# USBSocket_Type1_v1_0.net
KiCad netlist of a schematic drawn in EAGLE
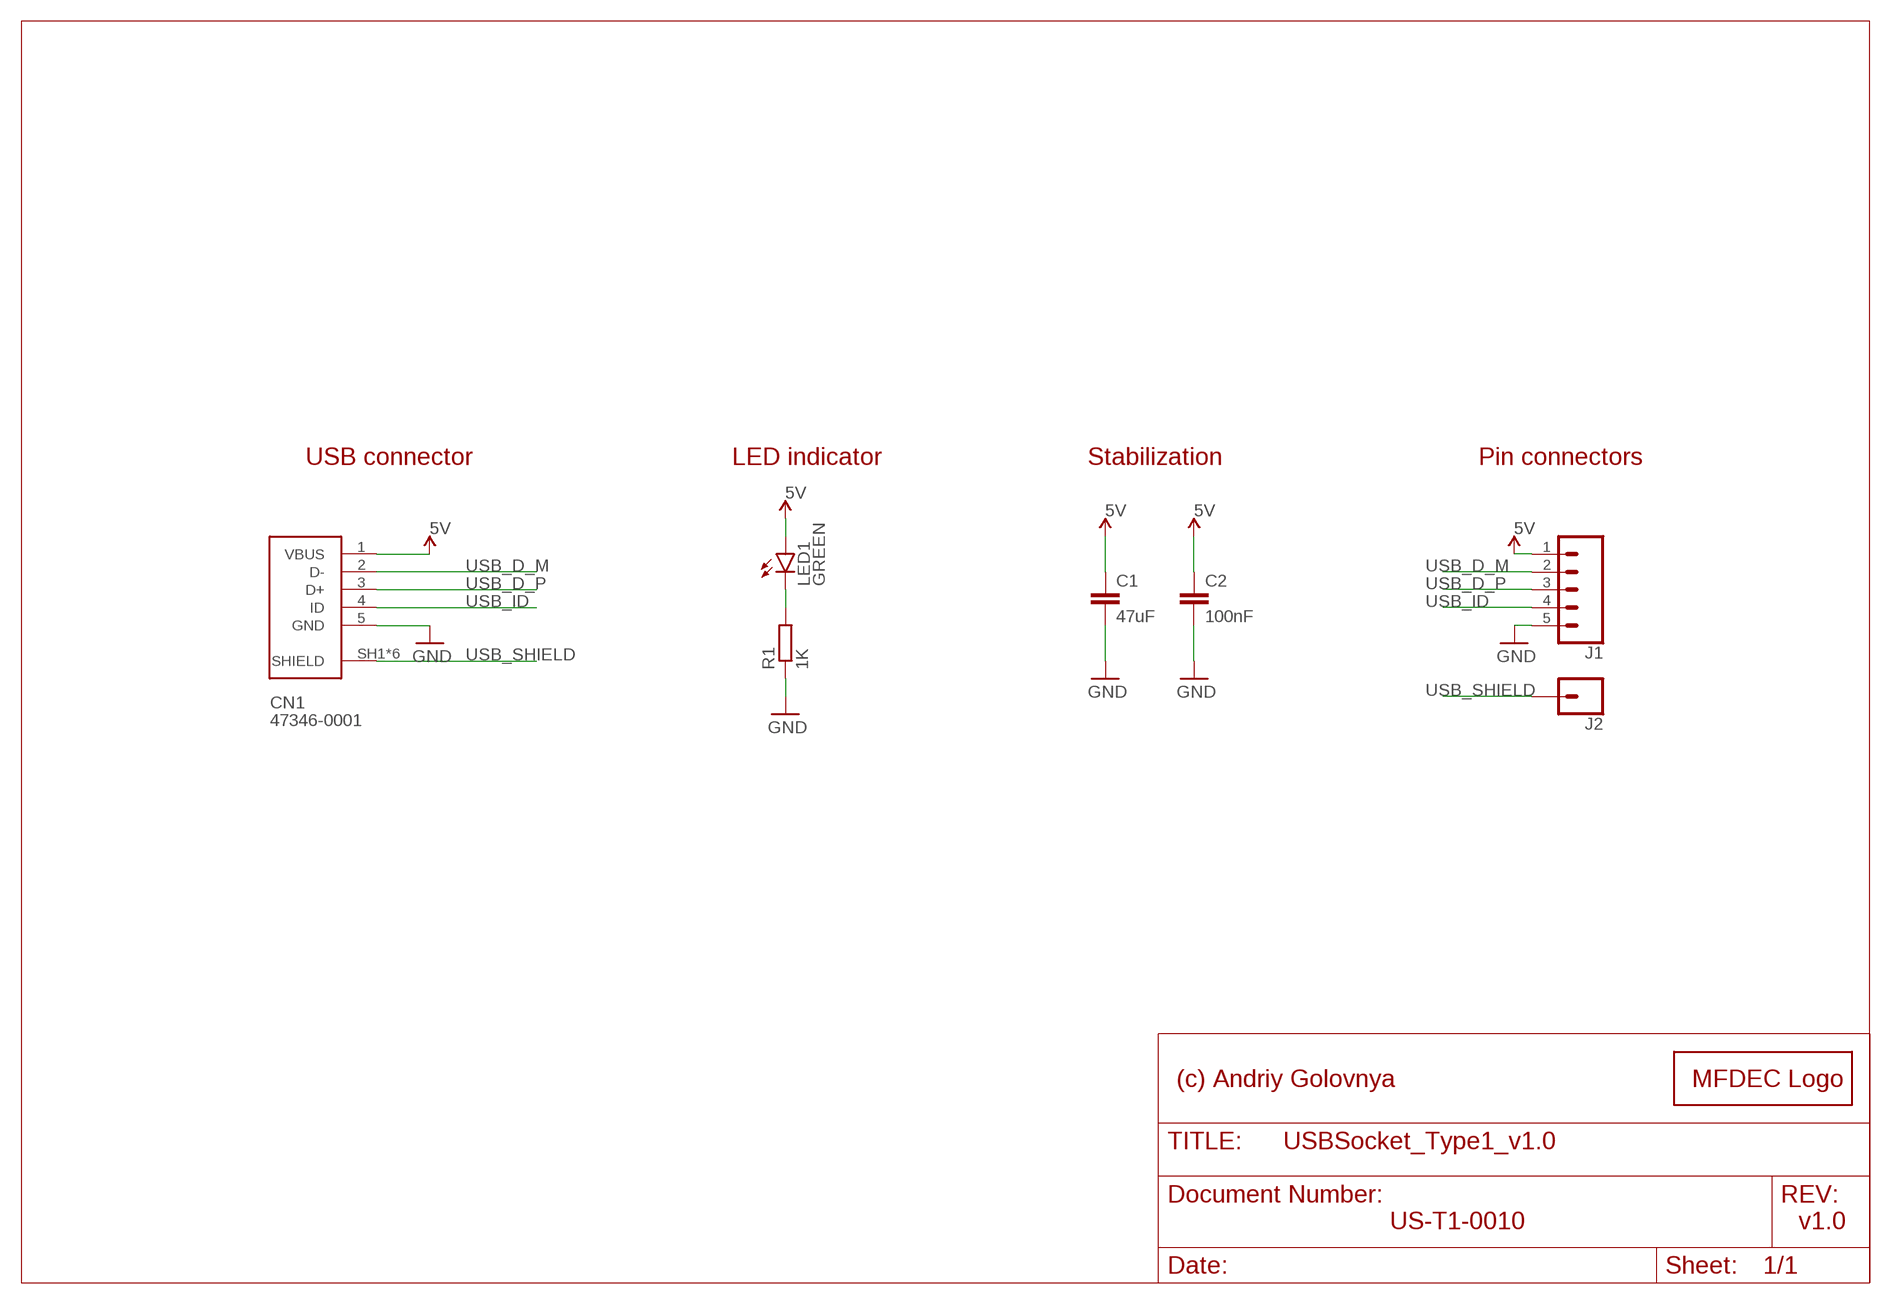
[diagram p0: schematic, sheet 1]

(export (version "E")
  (design (tool "Eeschema 10.0.6"))
  (components
    (comp (ref "C1")
      (value "47uF")
      (footprint "eagle-import:C0805")
      (libsource (lib "eagle-import") (part "C-EUC0805"))
    )
    (comp (ref "C2")
      (value "100nF")
      (footprint "eagle-import:C0402")
      (libsource (lib "eagle-import") (part "C-EUC0402"))
    )
    (comp (ref "CN1")
      (value "47346-0001")
      (footprint "eagle-import:MOLEX_47346-0001")
      (fields (field (name "MANUFACTURER") "Molex"))
      (libsource (lib "eagle-import") (part "47346-0001"))
    )
    (comp (ref "J1")
      (value "CONN_05PTH")
      (footprint "eagle-import:1X05")
      (libsource (lib "eagle-import") (part "CONN_05PTH"))
    )
    (comp (ref "J2")
      (value "CONN_01")
      (footprint "eagle-import:1X01")
      (libsource (lib "eagle-import") (part "CONN_01"))
    )
    (comp (ref "LED1")
      (value "GREEN")
      (footprint "eagle-import:SML0603")
      (libsource (lib "eagle-import") (part "LEDSML0603"))
    )
    (comp (ref "LOGO1")
      (value "MFDECLOGO_L_10MM")
      (footprint "eagle-import:MFDEC_L_10MM")
      (libsource (lib "eagle-import") (part "MFDECLOGO_L_10MM"))
    )
    (comp (ref "R1")
      (value "1K")
      (footprint "eagle-import:R0402")
      (libsource (lib "eagle-import") (part "R-EU_R0402"))
    )
  )
  (nets
    (net (code "1") (name "/USB_D_M") (class "Default")
      (node (ref "CN1") (pin "2") (pinfunction "D-_2") (pintype "bidirectional"))
      (node (ref "J1") (pin "2") (pinfunction "2_2") (pintype "passive"))
    )
    (net (code "2") (name "/USB_D_P") (class "Default")
      (node (ref "CN1") (pin "3") (pinfunction "D+_3") (pintype "bidirectional"))
      (node (ref "J1") (pin "3") (pinfunction "3_3") (pintype "passive"))
    )
    (net (code "3") (name "/USB_ID") (class "Default")
      (node (ref "CN1") (pin "4") (pinfunction "ID_4") (pintype "passive"))
      (node (ref "J1") (pin "4") (pinfunction "4_4") (pintype "passive"))
    )
    (net (code "4") (name "/USB_SHIELD") (class "Default")
      (node (ref "CN1") (pin "SH1") (pinfunction "SHIELD_SH1") (pintype "passive"))
      (node (ref "CN1") (pin "SH2") (pinfunction "SHIELD_SH2") (pintype "passive"))
      (node (ref "CN1") (pin "SH3") (pinfunction "SHIELD_SH3") (pintype "passive"))
      (node (ref "CN1") (pin "SH4") (pinfunction "SHIELD_SH4") (pintype "passive"))
      (node (ref "CN1") (pin "SH5") (pinfunction "SHIELD_SH5") (pintype "passive"))
      (node (ref "CN1") (pin "SH6") (pinfunction "SHIELD_SH6") (pintype "passive"))
      (node (ref "J2") (pin "1") (pinfunction "1_1") (pintype "passive"))
    )
    (net (code "5") (name "5V") (class "Default")
      (node (ref "C1") (pin "1") (pinfunction "1_1") (pintype "passive"))
      (node (ref "C2") (pin "1") (pinfunction "1_1") (pintype "passive"))
      (node (ref "CN1") (pin "1") (pinfunction "VBUS_1") (pintype "power_in"))
      (node (ref "J1") (pin "1") (pinfunction "1_1") (pintype "passive"))
      (node (ref "LED1") (pin "A") (pinfunction "A_A") (pintype "passive"))
    )
    (net (code "6") (name "GND") (class "Default")
      (node (ref "C1") (pin "2") (pinfunction "2_2") (pintype "passive"))
      (node (ref "C2") (pin "2") (pinfunction "2_2") (pintype "passive"))
      (node (ref "CN1") (pin "5") (pinfunction "GND_5") (pintype "power_in"))
      (node (ref "J1") (pin "5") (pinfunction "5_5") (pintype "passive"))
      (node (ref "R1") (pin "1") (pinfunction "1_1") (pintype "passive"))
    )
    (net (code "7") (name "Net-(LED1-PadC)") (class "Default")
      (node (ref "LED1") (pin "C") (pinfunction "C_C") (pintype "passive"))
      (node (ref "R1") (pin "2") (pinfunction "2_2") (pintype "passive"))
    )
  )
)
